# bone_capes.net
KiCad netlist of a schematic drawn in Altium Designer
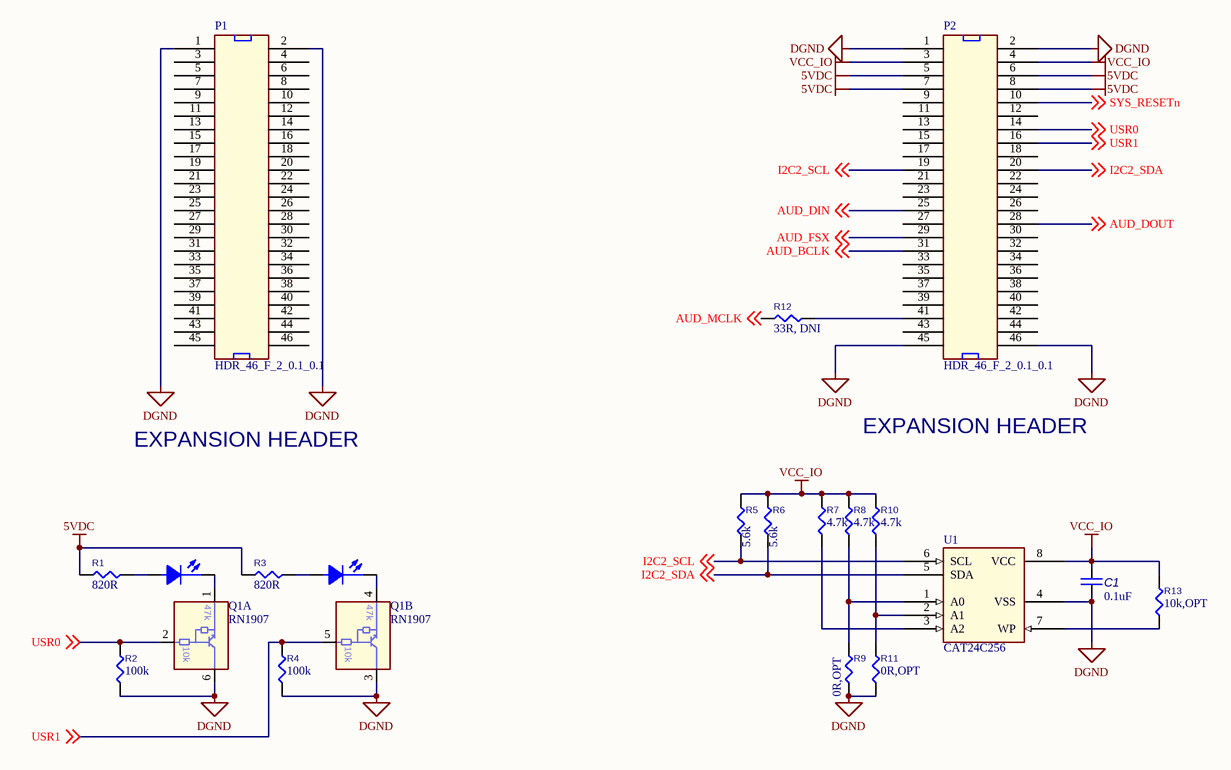
[diagram p0: bone_capes.SchDoc]

(export (version "E")
  (design (tool "Eeschema 10.0.6"))
  (components
    (comp (ref "C1")
      (value "0.1uF")
      (footprint "CC1608-0603")
      (description "C0603")
      (libsource (lib "usomiq-audio") (part "C0603"))
    )
    (comp (ref "D1")
      (value "LED0805")
      (footprint "LED0805")
      (description "LED 0805")
      (libsource (lib "am335x-base") (part "LED0805"))
    )
    (comp (ref "D2")
      (value "LED0805")
      (footprint "LED0805")
      (description "LED 0805")
      (libsource (lib "am335x-base") (part "LED0805"))
    )
    (comp (ref "P1")
      (value "HDR_46_F_2_0.1_0.1")
      (footprint "DIP46")
      (description "NN HEADER FMAL 46PS.1\" DL GOLD")
      (fields (field (name "MFR") "major league electronics"))
      (libsource (lib "usomiq-audio") (part "HDR_46_F_2_0.1_0.1"))
    )
    (comp (ref "P2")
      (value "HDR_46_F_2_0.1_0.1")
      (footprint "DIP46")
      (description "NN HEADER FMAL 46PS.1\" DL GOLD")
      (fields (field (name "MFR") "major league electronics"))
      (libsource (lib "usomiq-audio") (part "HDR_46_F_2_0.1_0.1"))
    )
    (comp (ref "Q1")
      (value "RN1907")
      (footprint "SOT363-6L")
      (description "Transistor Silicon NPN")
      (fields (field (name "MFR") "Panasonic"))
      (libsource (lib "am335x-base") (part "RN1907"))
    )
    (comp (ref "R1")
      (value "820R")
      (footprint "RESC1608X55N")
      (description "R0603")
      (libsource (lib "am335x-base") (part "R0603"))
    )
    (comp (ref "R2")
      (value "100k")
      (footprint "RESC1608X55N")
      (description "R0603")
      (libsource (lib "am335x-base") (part "R0603"))
    )
    (comp (ref "R3")
      (value "820R")
      (footprint "RESC1608X55N")
      (description "R0603")
      (libsource (lib "am335x-base") (part "R0603"))
    )
    (comp (ref "R4")
      (value "100k")
      (footprint "RESC1608X55N")
      (description "R0603")
      (libsource (lib "am335x-base") (part "R0603"))
    )
    (comp (ref "R5")
      (value "5.6k")
      (footprint "RESC1608X55N")
      (description "R0603")
      (libsource (lib "usomiq-audio") (part "R0603"))
    )
    (comp (ref "R6")
      (value "5.6k")
      (footprint "RESC1608X55N")
      (description "R0603")
      (libsource (lib "usomiq-audio") (part "R0603"))
    )
    (comp (ref "R7")
      (value "4.7k")
      (footprint "RESC1608X55N")
      (description "R0603")
      (libsource (lib "usomiq-audio") (part "R0603"))
    )
    (comp (ref "R8")
      (value "4.7k")
      (footprint "RESC1608X55N")
      (description "R0603")
      (libsource (lib "usomiq-audio") (part "R0603"))
    )
    (comp (ref "R9")
      (value "0R,OPT")
      (footprint "RESC1608X55N")
      (description "R0603")
      (libsource (lib "usomiq-audio") (part "R0603"))
    )
    (comp (ref "R10")
      (value "4.7k")
      (footprint "RESC1608X55N")
      (description "R0603")
      (libsource (lib "usomiq-audio") (part "R0603"))
    )
    (comp (ref "R11")
      (value "0R,OPT")
      (footprint "RESC1608X55N")
      (description "R0603")
      (libsource (lib "usomiq-audio") (part "R0603"))
    )
    (comp (ref "R12")
      (value "33R, DNI")
      (footprint "RESC1608X55N")
      (description "R0603")
      (libsource (lib "usomiq-audio") (part "R0603"))
    )
    (comp (ref "R13")
      (value "10k,OPT")
      (footprint "RESC1608X55N")
      (description "R0603")
      (libsource (lib "usomiq-audio") (part "R0603"))
    )
    (comp (ref "U1")
      (value "CAT24C256")
      (footprint "SOIC127P600X173-8L")
      (description "256 kb I2C CMOS Serial  EEPROM")
      (fields (field (name "MANUFACTURER") "ON Semiconductor"))
      (libsource (lib "usomiq-audio") (part "CAT24C256"))
    )
  )
  (nets
    (net (code "1") (name "5VDC") (class "Default")
      (node (ref "P2") (pin "5") (pinfunction "3_5") (pintype "passive"))
      (node (ref "P2") (pin "6") (pinfunction "28_6") (pintype "passive"))
      (node (ref "P2") (pin "7") (pinfunction "4_7") (pintype "passive"))
      (node (ref "P2") (pin "8") (pinfunction "29_8") (pintype "passive"))
      (node (ref "R1") (pin "2") (pinfunction "2_2") (pintype "passive"))
      (node (ref "R3") (pin "2") (pinfunction "2_2") (pintype "passive"))
    )
    (net (code "2") (name "AUD_BCLK") (class "Default")
      (node (ref "P2") (pin "31") (pinfunction "16_31") (pintype "passive"))
    )
    (net (code "3") (name "AUD_DIN") (class "Default")
      (node (ref "P2") (pin "25") (pinfunction "13_25") (pintype "passive"))
    )
    (net (code "4") (name "AUD_DOUT") (class "Default")
      (node (ref "P2") (pin "28") (pinfunction "39_28") (pintype "passive"))
    )
    (net (code "5") (name "AUD_FSX") (class "Default")
      (node (ref "P2") (pin "29") (pinfunction "15_29") (pintype "passive"))
    )
    (net (code "6") (name "AUD_MCLK") (class "Default")
      (node (ref "R12") (pin "1") (pinfunction "1_1") (pintype "passive"))
    )
    (net (code "7") (name "DGND") (class "Default")
      (node (ref "C1") (pin "2") (pinfunction "2_2") (pintype "passive"))
      (node (ref "P1") (pin "1") (pinfunction "1_1") (pintype "passive"))
      (node (ref "P1") (pin "2") (pinfunction "26_2") (pintype "passive"))
      (node (ref "P2") (pin "1") (pinfunction "1_1") (pintype "passive"))
      (node (ref "P2") (pin "2") (pinfunction "26_2") (pintype "passive"))
      (node (ref "P2") (pin "45") (pinfunction "23_45") (pintype "passive"))
      (node (ref "P2") (pin "46") (pinfunction "48_46") (pintype "passive"))
      (node (ref "Q1") (pin "3") (pinfunction "3_3") (pintype "passive"))
      (node (ref "Q1") (pin "6") (pinfunction "3_6") (pintype "passive"))
      (node (ref "R11") (pin "1") (pinfunction "1_1") (pintype "passive"))
      (node (ref "R2") (pin "1") (pinfunction "1_1") (pintype "passive"))
      (node (ref "R4") (pin "1") (pinfunction "1_1") (pintype "passive"))
      (node (ref "R9") (pin "1") (pinfunction "1_1") (pintype "passive"))
      (node (ref "U1") (pin "4") (pinfunction "VSS_4") (pintype "passive"))
    )
    (net (code "8") (name "I2C2_SCL") (class "Default")
      (node (ref "P2") (pin "19") (pinfunction "10_19") (pintype "passive"))
      (node (ref "R5") (pin "1") (pinfunction "1_1") (pintype "passive"))
      (node (ref "U1") (pin "6") (pinfunction "SCL_6") (pintype "input"))
    )
    (net (code "9") (name "I2C2_SDA") (class "Default")
      (node (ref "P2") (pin "20") (pinfunction "35_20") (pintype "passive"))
      (node (ref "R6") (pin "1") (pinfunction "1_1") (pintype "passive"))
      (node (ref "U1") (pin "5") (pinfunction "SDA_5") (pintype "passive"))
    )
    (net (code "10") (name "Net-(D1-A)") (class "Default")
      (node (ref "D1") (pin "1") (pinfunction "A_1") (pintype "passive"))
      (node (ref "R1") (pin "1") (pinfunction "1_1") (pintype "passive"))
    )
    (net (code "11") (name "Net-(D1-C)") (class "Default")
      (node (ref "D1") (pin "2") (pinfunction "C_2") (pintype "passive"))
      (node (ref "Q1") (pin "1") (pinfunction "4_1") (pintype "passive"))
    )
    (net (code "12") (name "Net-(D2-A)") (class "Default")
      (node (ref "D2") (pin "1") (pinfunction "A_1") (pintype "passive"))
      (node (ref "R3") (pin "1") (pinfunction "1_1") (pintype "passive"))
    )
    (net (code "13") (name "Net-(D2-C)") (class "Default")
      (node (ref "D2") (pin "2") (pinfunction "C_2") (pintype "passive"))
      (node (ref "Q1") (pin "4") (pinfunction "4_4") (pintype "passive"))
    )
    (net (code "14") (name "Net-(P2-21)") (class "Default")
      (node (ref "P2") (pin "41") (pinfunction "21_41") (pintype "passive"))
      (node (ref "R12") (pin "2") (pinfunction "2_2") (pintype "passive"))
    )
    (net (code "15") (name "Net-(U1-A0)") (class "Default")
      (node (ref "R8") (pin "1") (pinfunction "1_1") (pintype "passive"))
      (node (ref "R9") (pin "2") (pinfunction "2_2") (pintype "passive"))
      (node (ref "U1") (pin "1") (pinfunction "A0_1") (pintype "input"))
    )
    (net (code "16") (name "Net-(U1-A1)") (class "Default")
      (node (ref "R10") (pin "1") (pinfunction "1_1") (pintype "passive"))
      (node (ref "R11") (pin "2") (pinfunction "2_2") (pintype "passive"))
      (node (ref "U1") (pin "2") (pinfunction "A1_2") (pintype "input"))
    )
    (net (code "17") (name "Net-(U1-A2)") (class "Default")
      (node (ref "R7") (pin "1") (pinfunction "1_1") (pintype "passive"))
      (node (ref "U1") (pin "3") (pinfunction "A2_3") (pintype "input"))
    )
    (net (code "18") (name "Net-(U1-WP)") (class "Default")
      (node (ref "R13") (pin "1") (pinfunction "1_1") (pintype "passive"))
      (node (ref "U1") (pin "7") (pinfunction "WP_7") (pintype "input"))
    )
    (net (code "19") (name "SYS_RESETn") (class "Default")
      (node (ref "P2") (pin "10") (pinfunction "30_10") (pintype "passive"))
    )
    (net (code "20") (name "USR0") (class "Default")
      (node (ref "P2") (pin "14") (pinfunction "32_14") (pintype "passive"))
      (node (ref "Q1") (pin "2") (pinfunction "5_2") (pintype "passive"))
      (node (ref "R2") (pin "2") (pinfunction "2_2") (pintype "passive"))
    )
    (net (code "21") (name "USR1") (class "Default")
      (node (ref "P2") (pin "16") (pinfunction "33_16") (pintype "passive"))
      (node (ref "Q1") (pin "5") (pinfunction "5_5") (pintype "passive"))
      (node (ref "R4") (pin "2") (pinfunction "2_2") (pintype "passive"))
    )
    (net (code "22") (name "VCC_IO") (class "Default")
      (node (ref "C1") (pin "1") (pinfunction "1_1") (pintype "passive"))
      (node (ref "P2") (pin "3") (pinfunction "2_3") (pintype "passive"))
      (node (ref "P2") (pin "4") (pinfunction "27_4") (pintype "passive"))
      (node (ref "R10") (pin "2") (pinfunction "2_2") (pintype "passive"))
      (node (ref "R13") (pin "2") (pinfunction "2_2") (pintype "passive"))
      (node (ref "R5") (pin "2") (pinfunction "2_2") (pintype "passive"))
      (node (ref "R6") (pin "2") (pinfunction "2_2") (pintype "passive"))
      (node (ref "R7") (pin "2") (pinfunction "2_2") (pintype "passive"))
      (node (ref "R8") (pin "2") (pinfunction "2_2") (pintype "passive"))
      (node (ref "U1") (pin "8") (pinfunction "VCC_8") (pintype "passive"))
    )
    (net (code "23") (name "unconnected-(P1-2-Pad3)") (class "Default")
      (node (ref "P1") (pin "3") (pinfunction "2_3") (pintype "passive"))
    )
    (net (code "24") (name "unconnected-(P1-3-Pad5)") (class "Default")
      (node (ref "P1") (pin "5") (pinfunction "3_5") (pintype "passive"))
    )
    (net (code "25") (name "unconnected-(P1-4-Pad7)") (class "Default")
      (node (ref "P1") (pin "7") (pinfunction "4_7") (pintype "passive"))
    )
    (net (code "26") (name "unconnected-(P1-5-Pad9)") (class "Default")
      (node (ref "P1") (pin "9") (pinfunction "5_9") (pintype "passive"))
    )
    (net (code "27") (name "unconnected-(P1-6-Pad11)") (class "Default")
      (node (ref "P1") (pin "11") (pinfunction "6_11") (pintype "passive"))
    )
    (net (code "28") (name "unconnected-(P1-7-Pad13)") (class "Default")
      (node (ref "P1") (pin "13") (pinfunction "7_13") (pintype "passive"))
    )
    (net (code "29") (name "unconnected-(P1-8-Pad15)") (class "Default")
      (node (ref "P1") (pin "15") (pinfunction "8_15") (pintype "passive"))
    )
    (net (code "30") (name "unconnected-(P1-9-Pad17)") (class "Default")
      (node (ref "P1") (pin "17") (pinfunction "9_17") (pintype "passive"))
    )
    (net (code "31") (name "unconnected-(P1-10-Pad19)") (class "Default")
      (node (ref "P1") (pin "19") (pinfunction "10_19") (pintype "passive"))
    )
    (net (code "32") (name "unconnected-(P1-11-Pad21)") (class "Default")
      (node (ref "P1") (pin "21") (pinfunction "11_21") (pintype "passive"))
    )
    (net (code "33") (name "unconnected-(P1-12-Pad23)") (class "Default")
      (node (ref "P1") (pin "23") (pinfunction "12_23") (pintype "passive"))
    )
    (net (code "34") (name "unconnected-(P1-13-Pad25)") (class "Default")
      (node (ref "P1") (pin "25") (pinfunction "13_25") (pintype "passive"))
    )
    (net (code "35") (name "unconnected-(P1-14-Pad27)") (class "Default")
      (node (ref "P1") (pin "27") (pinfunction "14_27") (pintype "passive"))
    )
    (net (code "36") (name "unconnected-(P1-15-Pad29)") (class "Default")
      (node (ref "P1") (pin "29") (pinfunction "15_29") (pintype "passive"))
    )
    (net (code "37") (name "unconnected-(P1-16-Pad31)") (class "Default")
      (node (ref "P1") (pin "31") (pinfunction "16_31") (pintype "passive"))
    )
    (net (code "38") (name "unconnected-(P1-17-Pad33)") (class "Default")
      (node (ref "P1") (pin "33") (pinfunction "17_33") (pintype "passive"))
    )
    (net (code "39") (name "unconnected-(P1-18-Pad35)") (class "Default")
      (node (ref "P1") (pin "35") (pinfunction "18_35") (pintype "passive"))
    )
    (net (code "40") (name "unconnected-(P1-19-Pad37)") (class "Default")
      (node (ref "P1") (pin "37") (pinfunction "19_37") (pintype "passive"))
    )
    (net (code "41") (name "unconnected-(P1-20-Pad39)") (class "Default")
      (node (ref "P1") (pin "39") (pinfunction "20_39") (pintype "passive"))
    )
    (net (code "42") (name "unconnected-(P1-21-Pad41)") (class "Default")
      (node (ref "P1") (pin "41") (pinfunction "21_41") (pintype "passive"))
    )
    (net (code "43") (name "unconnected-(P1-22-Pad43)") (class "Default")
      (node (ref "P1") (pin "43") (pinfunction "22_43") (pintype "passive"))
    )
    (net (code "44") (name "unconnected-(P1-23-Pad45)") (class "Default")
      (node (ref "P1") (pin "45") (pinfunction "23_45") (pintype "passive"))
    )
    (net (code "45") (name "unconnected-(P1-27-Pad4)") (class "Default")
      (node (ref "P1") (pin "4") (pinfunction "27_4") (pintype "passive"))
    )
    (net (code "46") (name "unconnected-(P1-28-Pad6)") (class "Default")
      (node (ref "P1") (pin "6") (pinfunction "28_6") (pintype "passive"))
    )
    (net (code "47") (name "unconnected-(P1-29-Pad8)") (class "Default")
      (node (ref "P1") (pin "8") (pinfunction "29_8") (pintype "passive"))
    )
    (net (code "48") (name "unconnected-(P1-30-Pad10)") (class "Default")
      (node (ref "P1") (pin "10") (pinfunction "30_10") (pintype "passive"))
    )
    (net (code "49") (name "unconnected-(P1-31-Pad12)") (class "Default")
      (node (ref "P1") (pin "12") (pinfunction "31_12") (pintype "passive"))
    )
    (net (code "50") (name "unconnected-(P1-32-Pad14)") (class "Default")
      (node (ref "P1") (pin "14") (pinfunction "32_14") (pintype "passive"))
    )
    (net (code "51") (name "unconnected-(P1-33-Pad16)") (class "Default")
      (node (ref "P1") (pin "16") (pinfunction "33_16") (pintype "passive"))
    )
    (net (code "52") (name "unconnected-(P1-34-Pad18)") (class "Default")
      (node (ref "P1") (pin "18") (pinfunction "34_18") (pintype "passive"))
    )
    (net (code "53") (name "unconnected-(P1-35-Pad20)") (class "Default")
      (node (ref "P1") (pin "20") (pinfunction "35_20") (pintype "passive"))
    )
    (net (code "54") (name "unconnected-(P1-36-Pad22)") (class "Default")
      (node (ref "P1") (pin "22") (pinfunction "36_22") (pintype "passive"))
    )
    (net (code "55") (name "unconnected-(P1-37-Pad24)") (class "Default")
      (node (ref "P1") (pin "24") (pinfunction "37_24") (pintype "passive"))
    )
    (net (code "56") (name "unconnected-(P1-38-Pad26)") (class "Default")
      (node (ref "P1") (pin "26") (pinfunction "38_26") (pintype "passive"))
    )
    (net (code "57") (name "unconnected-(P1-39-Pad28)") (class "Default")
      (node (ref "P1") (pin "28") (pinfunction "39_28") (pintype "passive"))
    )
    (net (code "58") (name "unconnected-(P1-40-Pad30)") (class "Default")
      (node (ref "P1") (pin "30") (pinfunction "40_30") (pintype "passive"))
    )
    (net (code "59") (name "unconnected-(P1-41-Pad32)") (class "Default")
      (node (ref "P1") (pin "32") (pinfunction "41_32") (pintype "passive"))
    )
    (net (code "60") (name "unconnected-(P1-42-Pad34)") (class "Default")
      (node (ref "P1") (pin "34") (pinfunction "42_34") (pintype "passive"))
    )
    (net (code "61") (name "unconnected-(P1-43-Pad36)") (class "Default")
      (node (ref "P1") (pin "36") (pinfunction "43_36") (pintype "passive"))
    )
    (net (code "62") (name "unconnected-(P1-44-Pad38)") (class "Default")
      (node (ref "P1") (pin "38") (pinfunction "44_38") (pintype "passive"))
    )
    (net (code "63") (name "unconnected-(P1-45-Pad40)") (class "Default")
      (node (ref "P1") (pin "40") (pinfunction "45_40") (pintype "passive"))
    )
    (net (code "64") (name "unconnected-(P1-46-Pad42)") (class "Default")
      (node (ref "P1") (pin "42") (pinfunction "46_42") (pintype "passive"))
    )
    (net (code "65") (name "unconnected-(P1-47-Pad44)") (class "Default")
      (node (ref "P1") (pin "44") (pinfunction "47_44") (pintype "passive"))
    )
    (net (code "66") (name "unconnected-(P1-48-Pad46)") (class "Default")
      (node (ref "P1") (pin "46") (pinfunction "48_46") (pintype "passive"))
    )
    (net (code "67") (name "unconnected-(P2-5-Pad9)") (class "Default")
      (node (ref "P2") (pin "9") (pinfunction "5_9") (pintype "passive"))
    )
    (net (code "68") (name "unconnected-(P2-6-Pad11)") (class "Default")
      (node (ref "P2") (pin "11") (pinfunction "6_11") (pintype "passive"))
    )
    (net (code "69") (name "unconnected-(P2-7-Pad13)") (class "Default")
      (node (ref "P2") (pin "13") (pinfunction "7_13") (pintype "passive"))
    )
    (net (code "70") (name "unconnected-(P2-8-Pad15)") (class "Default")
      (node (ref "P2") (pin "15") (pinfunction "8_15") (pintype "passive"))
    )
    (net (code "71") (name "unconnected-(P2-9-Pad17)") (class "Default")
      (node (ref "P2") (pin "17") (pinfunction "9_17") (pintype "passive"))
    )
    (net (code "72") (name "unconnected-(P2-11-Pad21)") (class "Default")
      (node (ref "P2") (pin "21") (pinfunction "11_21") (pintype "passive"))
    )
    (net (code "73") (name "unconnected-(P2-12-Pad23)") (class "Default")
      (node (ref "P2") (pin "23") (pinfunction "12_23") (pintype "passive"))
    )
    (net (code "74") (name "unconnected-(P2-14-Pad27)") (class "Default")
      (node (ref "P2") (pin "27") (pinfunction "14_27") (pintype "passive"))
    )
    (net (code "75") (name "unconnected-(P2-17-Pad33)") (class "Default")
      (node (ref "P2") (pin "33") (pinfunction "17_33") (pintype "passive"))
    )
    (net (code "76") (name "unconnected-(P2-18-Pad35)") (class "Default")
      (node (ref "P2") (pin "35") (pinfunction "18_35") (pintype "passive"))
    )
    (net (code "77") (name "unconnected-(P2-19-Pad37)") (class "Default")
      (node (ref "P2") (pin "37") (pinfunction "19_37") (pintype "passive"))
    )
    (net (code "78") (name "unconnected-(P2-20-Pad39)") (class "Default")
      (node (ref "P2") (pin "39") (pinfunction "20_39") (pintype "passive"))
    )
    (net (code "79") (name "unconnected-(P2-22-Pad43)") (class "Default")
      (node (ref "P2") (pin "43") (pinfunction "22_43") (pintype "passive"))
    )
    (net (code "80") (name "unconnected-(P2-31-Pad12)") (class "Default")
      (node (ref "P2") (pin "12") (pinfunction "31_12") (pintype "passive"))
    )
    (net (code "81") (name "unconnected-(P2-34-Pad18)") (class "Default")
      (node (ref "P2") (pin "18") (pinfunction "34_18") (pintype "passive"))
    )
    (net (code "82") (name "unconnected-(P2-36-Pad22)") (class "Default")
      (node (ref "P2") (pin "22") (pinfunction "36_22") (pintype "passive"))
    )
    (net (code "83") (name "unconnected-(P2-37-Pad24)") (class "Default")
      (node (ref "P2") (pin "24") (pinfunction "37_24") (pintype "passive"))
    )
    (net (code "84") (name "unconnected-(P2-38-Pad26)") (class "Default")
      (node (ref "P2") (pin "26") (pinfunction "38_26") (pintype "passive"))
    )
    (net (code "85") (name "unconnected-(P2-40-Pad30)") (class "Default")
      (node (ref "P2") (pin "30") (pinfunction "40_30") (pintype "passive"))
    )
    (net (code "86") (name "unconnected-(P2-41-Pad32)") (class "Default")
      (node (ref "P2") (pin "32") (pinfunction "41_32") (pintype "passive"))
    )
    (net (code "87") (name "unconnected-(P2-42-Pad34)") (class "Default")
      (node (ref "P2") (pin "34") (pinfunction "42_34") (pintype "passive"))
    )
    (net (code "88") (name "unconnected-(P2-43-Pad36)") (class "Default")
      (node (ref "P2") (pin "36") (pinfunction "43_36") (pintype "passive"))
    )
    (net (code "89") (name "unconnected-(P2-44-Pad38)") (class "Default")
      (node (ref "P2") (pin "38") (pinfunction "44_38") (pintype "passive"))
    )
    (net (code "90") (name "unconnected-(P2-45-Pad40)") (class "Default")
      (node (ref "P2") (pin "40") (pinfunction "45_40") (pintype "passive"))
    )
    (net (code "91") (name "unconnected-(P2-46-Pad42)") (class "Default")
      (node (ref "P2") (pin "42") (pinfunction "46_42") (pintype "passive"))
    )
    (net (code "92") (name "unconnected-(P2-47-Pad44)") (class "Default")
      (node (ref "P2") (pin "44") (pinfunction "47_44") (pintype "passive"))
    )
  )
)
